# VC8Evrs4.net
KiCad netlist of a schematic drawn in EAGLE
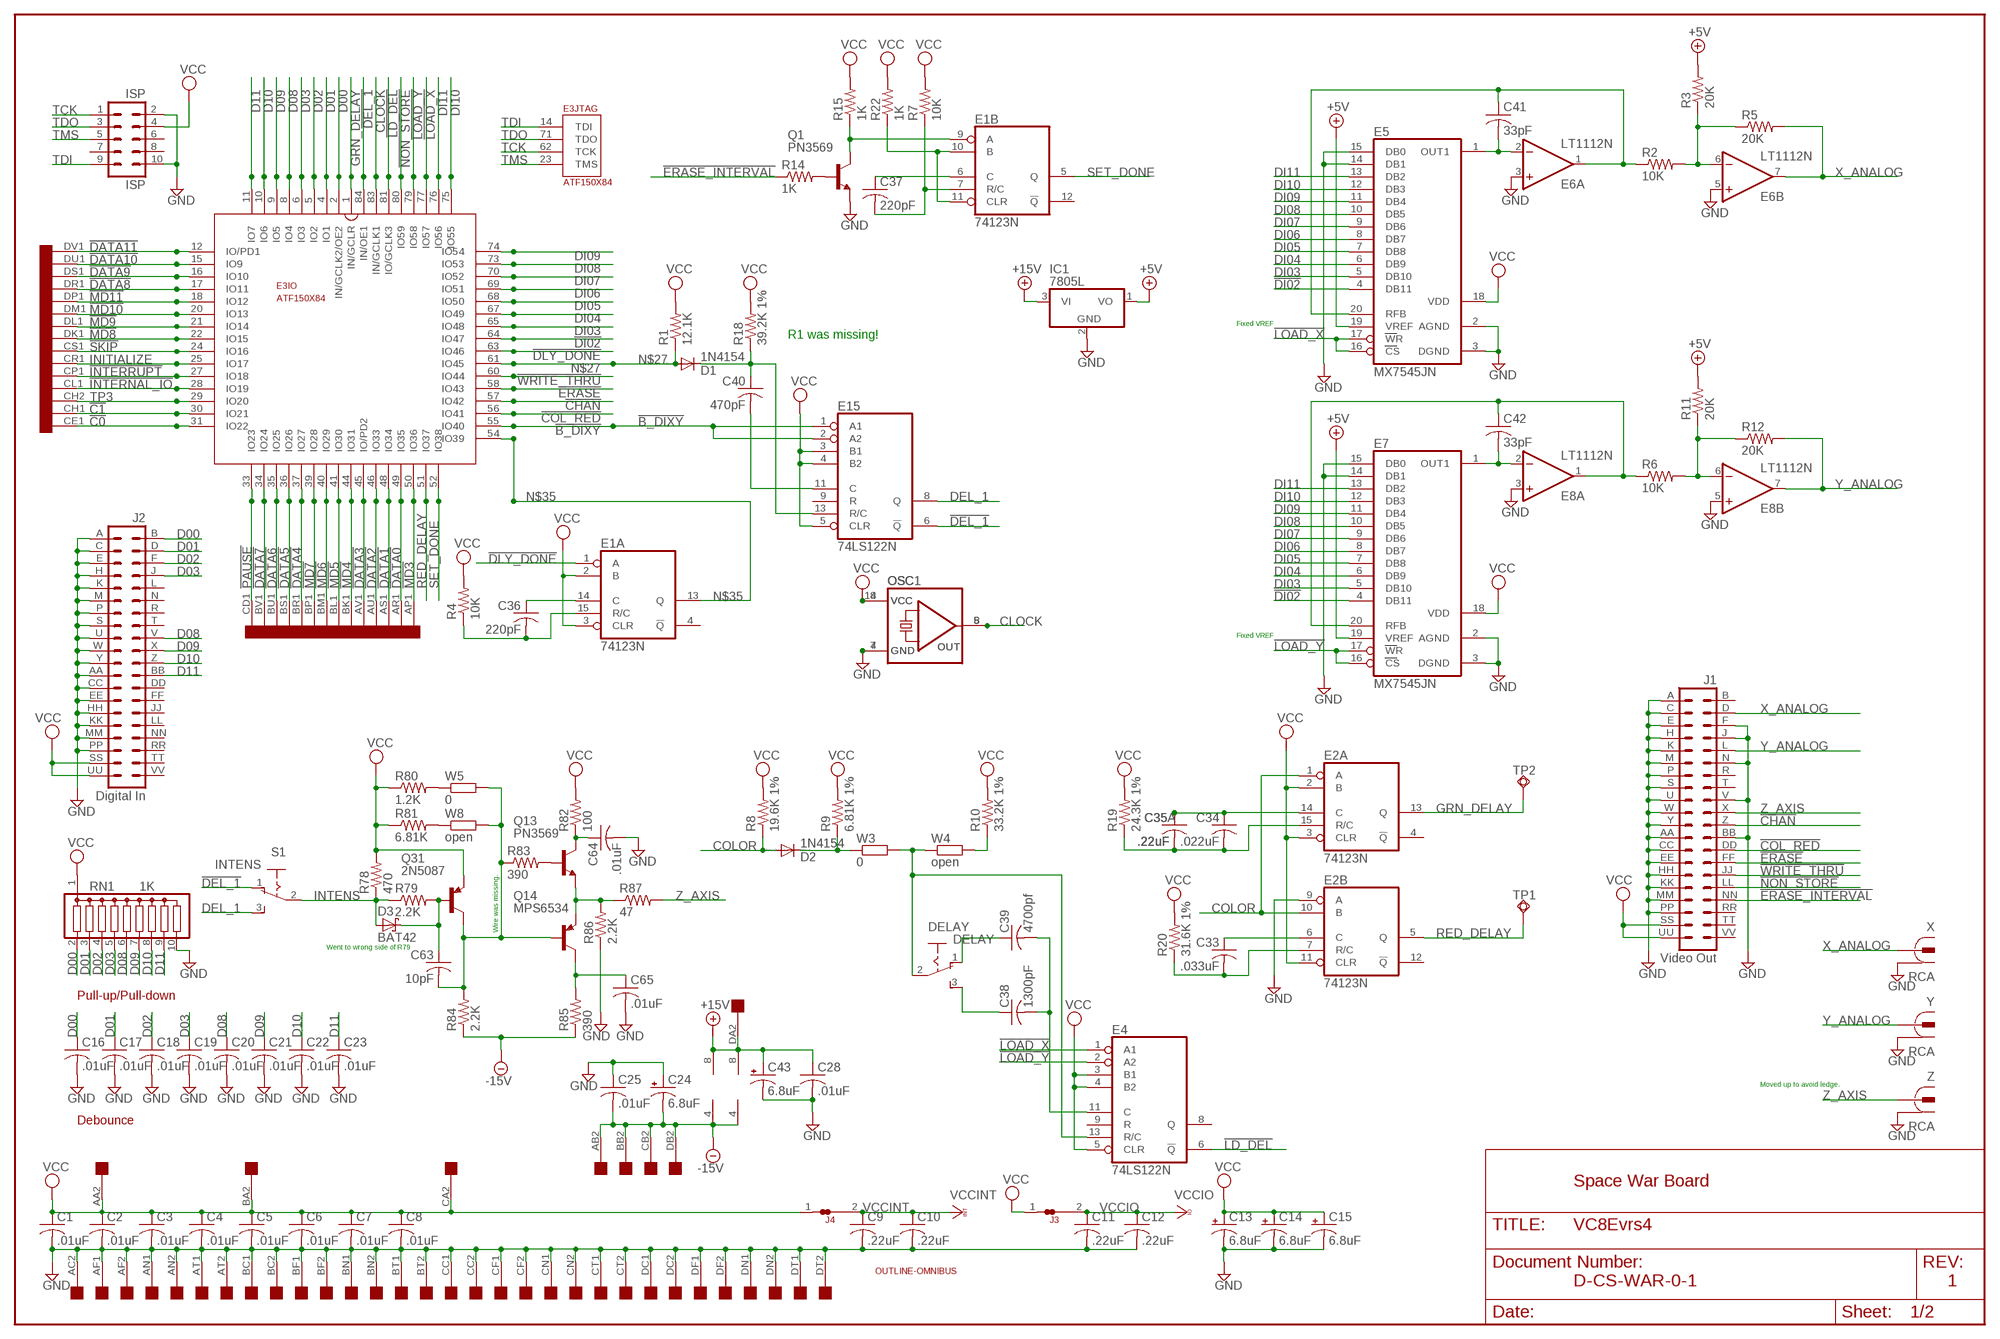
[diagram p0: schematic, sheet 1]

(export (version "E")
  (design (tool "Eeschema 10.0.6"))
  (components
    (comp (ref "C1")
      (value ".01uF")
      (footprint "eagle-import:C063-025X075")
      (libsource (lib "eagle-import") (part "C-US"))
    )
    (comp (ref "C2")
      (value ".01uF")
      (footprint "eagle-import:C063-025X075")
      (libsource (lib "eagle-import") (part "C-US"))
    )
    (comp (ref "C3")
      (value ".01uF")
      (footprint "eagle-import:C063-025X075")
      (libsource (lib "eagle-import") (part "C-US"))
    )
    (comp (ref "C4")
      (value ".01uF")
      (footprint "eagle-import:C063-025X075")
      (libsource (lib "eagle-import") (part "C-US"))
    )
    (comp (ref "C5")
      (value ".01uF")
      (footprint "eagle-import:C063-025X075")
      (libsource (lib "eagle-import") (part "C-US"))
    )
    (comp (ref "C6")
      (value ".01uF")
      (footprint "eagle-import:C063-025X075")
      (libsource (lib "eagle-import") (part "C-US"))
    )
    (comp (ref "C7")
      (value ".01uF")
      (footprint "eagle-import:C063-025X075")
      (libsource (lib "eagle-import") (part "C-US"))
    )
    (comp (ref "C8")
      (value ".01uF")
      (footprint "eagle-import:C063-025X075")
      (libsource (lib "eagle-import") (part "C-US"))
    )
    (comp (ref "C9")
      (value ".22uF")
      (footprint "eagle-import:C063-025X075")
      (libsource (lib "eagle-import") (part "C-US"))
    )
    (comp (ref "C10")
      (value ".22uF")
      (footprint "eagle-import:C063-025X075")
      (libsource (lib "eagle-import") (part "C-US"))
    )
    (comp (ref "C11")
      (value ".22uF")
      (footprint "eagle-import:C063-025X075")
      (libsource (lib "eagle-import") (part "C-US"))
    )
    (comp (ref "C12")
      (value ".22uF")
      (footprint "eagle-import:C063-025X075")
      (libsource (lib "eagle-import") (part "C-US"))
    )
    (comp (ref "C13")
      (value "6.8uF")
      (footprint "eagle-import:E12-8")
      (libsource (lib "eagle-import") (part "CPOL-USE20-8AXIAL"))
    )
    (comp (ref "C14")
      (value "6.8uF")
      (footprint "eagle-import:E12-8")
      (libsource (lib "eagle-import") (part "CPOL-USE20-8AXIAL"))
    )
    (comp (ref "C15")
      (value "6.8uF")
      (footprint "eagle-import:E12-8")
      (libsource (lib "eagle-import") (part "CPOL-USE20-8AXIAL"))
    )
    (comp (ref "C16")
      (value ".01uF")
      (footprint "eagle-import:C063-025X075")
      (libsource (lib "eagle-import") (part "C-US"))
    )
    (comp (ref "C17")
      (value ".01uF")
      (footprint "eagle-import:C063-025X075")
      (libsource (lib "eagle-import") (part "C-US"))
    )
    (comp (ref "C18")
      (value ".01uF")
      (footprint "eagle-import:C063-025X075")
      (libsource (lib "eagle-import") (part "C-US"))
    )
    (comp (ref "C19")
      (value ".01uF")
      (footprint "eagle-import:C063-025X075")
      (libsource (lib "eagle-import") (part "C-US"))
    )
    (comp (ref "C20")
      (value ".01uF")
      (footprint "eagle-import:C063-025X075")
      (libsource (lib "eagle-import") (part "C-US"))
    )
    (comp (ref "C21")
      (value ".01uF")
      (footprint "eagle-import:C063-025X075")
      (libsource (lib "eagle-import") (part "C-US"))
    )
    (comp (ref "C22")
      (value ".01uF")
      (footprint "eagle-import:C063-025X075")
      (libsource (lib "eagle-import") (part "C-US"))
    )
    (comp (ref "C23")
      (value ".01uF")
      (footprint "eagle-import:C063-025X075")
      (libsource (lib "eagle-import") (part "C-US"))
    )
    (comp (ref "C24")
      (value "6.8uF")
      (footprint "eagle-import:E12-8")
      (libsource (lib "eagle-import") (part "CPOL-USE20-8AXIAL"))
    )
    (comp (ref "C25")
      (value ".01uF")
      (footprint "eagle-import:C063-025X075")
      (libsource (lib "eagle-import") (part "C-US"))
    )
    (comp (ref "C28")
      (value ".01uF")
      (footprint "eagle-import:C063-025X075")
      (libsource (lib "eagle-import") (part "C-US"))
    )
    (comp (ref "C33")
      (value ".033uF")
      (footprint "eagle-import:C102-043X133")
      (libsource (lib "eagle-import") (part "C-US102-043X133"))
    )
    (comp (ref "C34")
      (value ".022uF")
      (footprint "eagle-import:C102-043X133")
      (libsource (lib "eagle-import") (part "C-US102-043X133"))
    )
    (comp (ref "C35")
      (value ".22uF")
      (footprint "eagle-import:C050-025X075")
      (libsource (lib "eagle-import") (part "C-US050-025X075"))
    )
    (comp (ref "C35A")
      (value ".22uF")
      (footprint "eagle-import:C102-043X133")
      (libsource (lib "eagle-import") (part "C-US102-043X133"))
    )
    (comp (ref "C36")
      (value "220pF")
      (footprint "eagle-import:C063-025X075")
      (libsource (lib "eagle-import") (part "C-US"))
    )
    (comp (ref "C37")
      (value "220pF")
      (footprint "eagle-import:C063-025X075")
      (libsource (lib "eagle-import") (part "C-US"))
    )
    (comp (ref "C38")
      (value "1300pF")
      (footprint "eagle-import:C150-054X183")
      (libsource (lib "eagle-import") (part "C-US150-054X183"))
    )
    (comp (ref "C39")
      (value "4700pf")
      (footprint "eagle-import:C102-043X133")
      (libsource (lib "eagle-import") (part "C-US102-043X133"))
    )
    (comp (ref "C40")
      (value "470pF")
      (footprint "eagle-import:C063-025X075")
      (libsource (lib "eagle-import") (part "C-US"))
    )
    (comp (ref "C41")
      (value "33pF")
      (footprint "eagle-import:C063-025X075")
      (libsource (lib "eagle-import") (part "C-US"))
    )
    (comp (ref "C42")
      (value "33pF")
      (footprint "eagle-import:C063-025X075")
      (libsource (lib "eagle-import") (part "C-US"))
    )
    (comp (ref "C43")
      (value "6.8uF")
      (footprint "eagle-import:E12-8")
      (libsource (lib "eagle-import") (part "CPOL-USE20-8AXIAL"))
    )
    (comp (ref "C63")
      (value "10pF")
      (footprint "eagle-import:C063-025X075")
      (libsource (lib "eagle-import") (part "C-US"))
    )
    (comp (ref "C64")
      (value ".01uF")
      (footprint "eagle-import:C063-025X075")
      (libsource (lib "eagle-import") (part "C-US"))
    )
    (comp (ref "C65")
      (value ".01uF")
      (footprint "eagle-import:C063-025X075")
      (libsource (lib "eagle-import") (part "C-US"))
    )
    (comp (ref "D1")
      (value "1N4154")
      (footprint "eagle-import:DO35-10")
      (libsource (lib "eagle-import") (part "DIODE-DO35-10"))
    )
    (comp (ref "D2")
      (value "1N4154")
      (footprint "eagle-import:DO35-10")
      (libsource (lib "eagle-import") (part "DIODE-DO35-10"))
    )
    (comp (ref "D3")
      (value "BAT42")
      (footprint "eagle-import:DO35-10")
      (libsource (lib "eagle-import") (part "BAT42"))
    )
    (comp (ref "DELAY")
      (value "DELAY")
      (footprint "eagle-import:M251")
      (libsource (lib "eagle-import") (part "M251"))
    )
    (comp (ref "E1")
      (value "74123N")
      (footprint "eagle-import:DIL16")
      (libsource (lib "eagle-import") (part "74123N"))
    )
    (comp (ref "E2")
      (value "74123N")
      (footprint "eagle-import:DIL16")
      (libsource (lib "eagle-import") (part "74123N"))
    )
    (comp (ref "E3")
      (value "ATF150X84")
      (footprint "eagle-import:S84")
      (libsource (lib "eagle-import") (part "ATF150X84"))
    )
    (comp (ref "E4")
      (value "74LS122N")
      (footprint "eagle-import:DIL14")
      (libsource (lib "eagle-import") (part "74122NLS"))
    )
    (comp (ref "E5")
      (value "MX7545JN")
      (footprint "eagle-import:DIL20")
      (fields (field (name "MPN") "MX7545JN+"))
      (libsource (lib "eagle-import") (part "MX7545JN"))
    )
    (comp (ref "E6")
      (value "LT1112N")
      (footprint "eagle-import:DIL08")
      (libsource (lib "eagle-import") (part "1458NLM"))
    )
    (comp (ref "E7")
      (value "MX7545JN")
      (footprint "eagle-import:DIL20")
      (fields (field (name "MPN") "MX7545JN+"))
      (libsource (lib "eagle-import") (part "MX7545JN"))
    )
    (comp (ref "E8")
      (value "LT1112N")
      (footprint "eagle-import:DIL08")
      (libsource (lib "eagle-import") (part "1458NLM"))
    )
    (comp (ref "E15")
      (value "74LS122N")
      (footprint "eagle-import:DIL14")
      (libsource (lib "eagle-import") (part "74122NLS"))
    )
    (comp (ref "IC1")
      (value "7805L")
      (footprint "eagle-import:TO92")
      (libsource (lib "eagle-import") (part "78L05"))
    )
    (comp (ref "ISP")
      (value "ISP")
      (footprint "eagle-import:ML10")
      (libsource (lib "eagle-import") (part "ML10"))
    )
    (comp (ref "J1")
      (value "Video Out")
      (footprint "eagle-import:DEC40PINH")
      (libsource (lib "eagle-import") (part "DEC40PINH"))
    )
    (comp (ref "J2")
      (value "Digital In")
      (footprint "eagle-import:DEC40PINH")
      (libsource (lib "eagle-import") (part "DEC40PINH"))
    )
    (comp (ref "J3")
      (value "JUMPER-NC1")
      (footprint "eagle-import:NC1")
      (libsource (lib "eagle-import") (part "JUMPER-NC1"))
    )
    (comp (ref "J4")
      (value "JUMPER-NC1")
      (footprint "eagle-import:NC1")
      (libsource (lib "eagle-import") (part "JUMPER-NC1"))
    )
    (comp (ref "OMNIBUS")
      (value "QUAD")
      (footprint "eagle-import:EDGE-CON8")
      (libsource (lib "eagle-import") (part "QUAD"))
    )
    (comp (ref "OSC")
      (value "QG5460")
      (footprint "eagle-import:DIL08S")
      (libsource (lib "eagle-import") (part "QG5460"))
    )
    (comp (ref "OSC1")
      (value "QG5860")
      (footprint "eagle-import:DIL14S")
      (libsource (lib "eagle-import") (part "QG5860"))
    )
    (comp (ref "Q1")
      (value "PN3569")
      (footprint "eagle-import:TO5")
      (libsource (lib "eagle-import") (part "-NPN-TO5"))
    )
    (comp (ref "Q13")
      (value "PN3569")
      (footprint "eagle-import:TO5")
      (libsource (lib "eagle-import") (part "-NPN-TO5"))
    )
    (comp (ref "Q14")
      (value "MPS6534")
      (footprint "eagle-import:TO5")
      (libsource (lib "eagle-import") (part "-PNP-TO5"))
    )
    (comp (ref "Q31")
      (value "2N5087")
      (footprint "eagle-import:TO5")
      (libsource (lib "eagle-import") (part "-PNP-TO5"))
    )
    (comp (ref "R1")
      (value "12.1K")
      (footprint "eagle-import:0207_15")
      (libsource (lib "eagle-import") (part "R-US_0207/15"))
    )
    (comp (ref "R2")
      (value "10K")
      (footprint "eagle-import:0207_10")
      (libsource (lib "eagle-import") (part "R-US_0207/10"))
    )
    (comp (ref "R3")
      (value "20K")
      (footprint "eagle-import:0207_10")
      (libsource (lib "eagle-import") (part "R-US_0207/10"))
    )
    (comp (ref "R4")
      (value "10K")
      (footprint "eagle-import:0207_10")
      (libsource (lib "eagle-import") (part "R-US_0207/10"))
    )
    (comp (ref "R5")
      (value "20K")
      (footprint "eagle-import:0207_10")
      (libsource (lib "eagle-import") (part "R-US_0207/10"))
    )
    (comp (ref "R6")
      (value "10K")
      (footprint "eagle-import:0207_10")
      (libsource (lib "eagle-import") (part "R-US_0207/10"))
    )
    (comp (ref "R7")
      (value "10K")
      (footprint "eagle-import:0207_10")
      (libsource (lib "eagle-import") (part "R-US_0207/10"))
    )
    (comp (ref "R8")
      (value "19.6K 1%")
      (footprint "eagle-import:0207_15")
      (libsource (lib "eagle-import") (part "R-US_0207/15"))
    )
    (comp (ref "R9")
      (value "6.81K 1%")
      (footprint "eagle-import:0207_15")
      (libsource (lib "eagle-import") (part "R-US_0207/15"))
    )
    (comp (ref "R10")
      (value "33.2K 1%")
      (footprint "eagle-import:0207_15")
      (libsource (lib "eagle-import") (part "R-US_0207/15"))
    )
    (comp (ref "R11")
      (value "20K")
      (footprint "eagle-import:0207_10")
      (libsource (lib "eagle-import") (part "R-US_0207/10"))
    )
    (comp (ref "R12")
      (value "20K")
      (footprint "eagle-import:0207_10")
      (libsource (lib "eagle-import") (part "R-US_0207/10"))
    )
    (comp (ref "R14")
      (value "1K")
      (footprint "eagle-import:0207_10")
      (libsource (lib "eagle-import") (part "R-US_0207/10"))
    )
    (comp (ref "R15")
      (value "1K")
      (footprint "eagle-import:0207_10")
      (libsource (lib "eagle-import") (part "R-US_0207/10"))
    )
    (comp (ref "R18")
      (value "39.2K 1%")
      (footprint "eagle-import:0207_15")
      (libsource (lib "eagle-import") (part "R-US_0207/15"))
    )
    (comp (ref "R19")
      (value "24.3K 1%")
      (footprint "eagle-import:0207_15")
      (libsource (lib "eagle-import") (part "R-US_0207/15"))
    )
    (comp (ref "R20")
      (value "31.6K 1%")
      (footprint "eagle-import:0207_15")
      (libsource (lib "eagle-import") (part "R-US_0207/15"))
    )
    (comp (ref "R22")
      (value "1K")
      (footprint "eagle-import:0207_10")
      (libsource (lib "eagle-import") (part "R-US_0207/10"))
    )
    (comp (ref "R78")
      (value "470")
      (footprint "eagle-import:0207_10")
      (libsource (lib "eagle-import") (part "R-US_0207/10"))
    )
    (comp (ref "R79")
      (value "2.2K")
      (footprint "eagle-import:0207_10")
      (libsource (lib "eagle-import") (part "R-US_0207/10"))
    )
    (comp (ref "R80")
      (value "1.2K")
      (footprint "eagle-import:0207_10")
      (libsource (lib "eagle-import") (part "R-US_0207/10"))
    )
    (comp (ref "R81")
      (value "6.81K")
      (footprint "eagle-import:0207_10")
      (libsource (lib "eagle-import") (part "R-US_0207/10"))
    )
    (comp (ref "R82")
      (value "100")
      (footprint "eagle-import:0207_10")
      (libsource (lib "eagle-import") (part "R-US_0207/10"))
    )
    (comp (ref "R83")
      (value "390")
      (footprint "eagle-import:0207_10")
      (libsource (lib "eagle-import") (part "R-US_0207/10"))
    )
    (comp (ref "R84")
      (value "2.2K")
      (footprint "eagle-import:0207_10")
      (libsource (lib "eagle-import") (part "R-US_0207/10"))
    )
    (comp (ref "R85")
      (value "390")
      (footprint "eagle-import:0207_10")
      (libsource (lib "eagle-import") (part "R-US_0207/10"))
    )
    (comp (ref "R86")
      (value "2.2K")
      (footprint "eagle-import:0207_10")
      (libsource (lib "eagle-import") (part "R-US_0207/10"))
    )
    (comp (ref "R87")
      (value "47")
      (footprint "eagle-import:0207_10")
      (libsource (lib "eagle-import") (part "R-US_0207/10"))
    )
    (comp (ref "RN1")
      (value "1K")
      (footprint "eagle-import:SIL10")
      (libsource (lib "eagle-import") (part "G09R"))
    )
    (comp (ref "S1")
      (value "INTENS")
      (footprint "eagle-import:M251")
      (libsource (lib "eagle-import") (part "M251"))
    )
    (comp (ref "TP1")
      (value "TPSQPAD1-17")
      (footprint "eagle-import:P1-17")
      (libsource (lib "eagle-import") (part "TPSQPAD1-17"))
    )
    (comp (ref "TP2")
      (value "TPSQPAD1-17")
      (footprint "eagle-import:P1-17")
      (libsource (lib "eagle-import") (part "TPSQPAD1-17"))
    )
    (comp (ref "U$1")
      (value "OUTLINE-OMNIBUS")
      (footprint "eagle-import:OMNIBUS")
      (libsource (lib "eagle-import") (part "OUTLINE-OMNIBUS"))
    )
    (comp (ref "W3")
      (value "0")
      (footprint "eagle-import:0207_10")
      (libsource (lib "eagle-import") (part "R-EU_0207/10"))
    )
    (comp (ref "W4")
      (value "open")
      (footprint "eagle-import:0207_10")
      (libsource (lib "eagle-import") (part "R-EU_0207/10"))
    )
    (comp (ref "W5")
      (value "0")
      (footprint "eagle-import:0207_10")
      (libsource (lib "eagle-import") (part "R-EU_0207/10"))
    )
    (comp (ref "W8")
      (value "open")
      (footprint "eagle-import:0207_10")
      (libsource (lib "eagle-import") (part "R-EU_0207/10"))
    )
    (comp (ref "X")
      (value "RCA")
      (footprint "eagle-import:RCA")
      (libsource (lib "eagle-import") (part "RCA"))
    )
    (comp (ref "Y")
      (value "RCA")
      (footprint "eagle-import:RCA")
      (libsource (lib "eagle-import") (part "RCA"))
    )
    (comp (ref "Z")
      (value "RCA")
      (footprint "eagle-import:RCA")
      (libsource (lib "eagle-import") (part "RCA"))
    )
  )
  (nets
    (net (code "1") (name "+5V") (class "Default")
      (node (ref "E5") (pin "19") (pinfunction "VREF_19") (pintype "input"))
      (node (ref "E7") (pin "19") (pinfunction "VREF_19") (pintype "input"))
      (node (ref "IC1") (pin "1") (pinfunction "VO_1") (pintype "passive"))
      (node (ref "R11") (pin "2") (pinfunction "2_2") (pintype "passive"))
      (node (ref "R3") (pin "2") (pinfunction "2_2") (pintype "passive"))
    )
    (net (code "2") (name "+15V") (class "Default")
      (node (ref "C28") (pin "1") (pinfunction "1_1") (pintype "passive"))
      (node (ref "C43") (pin "+") (pinfunction "+_+") (pintype "passive"))
      (node (ref "E6") (pin "8") (pinfunction "V+_8") (pintype "power_in"))
      (node (ref "E8") (pin "8") (pinfunction "V+_8") (pintype "power_in"))
      (node (ref "IC1") (pin "3") (pinfunction "VI_3") (pintype "input"))
      (node (ref "OMNIBUS") (pin "DA2") (pinfunction "1_DA2") (pintype "bidirectional"))
    )
    (net (code "3") (name "-15V") (class "Default")
      (node (ref "C24") (pin "-") (pinfunction "-_-") (pintype "passive"))
      (node (ref "C25") (pin "2") (pinfunction "2_2") (pintype "passive"))
      (node (ref "E6") (pin "4") (pinfunction "V-_4") (pintype "power_in"))
      (node (ref "E8") (pin "4") (pinfunction "V-_4") (pintype "power_in"))
      (node (ref "OMNIBUS") (pin "AB2") (pinfunction "1_AB2") (pintype "bidirectional"))
      (node (ref "OMNIBUS") (pin "BB2") (pinfunction "1_BB2") (pintype "bidirectional"))
      (node (ref "OMNIBUS") (pin "CB2") (pinfunction "1_CB2") (pintype "bidirectional"))
      (node (ref "OMNIBUS") (pin "DB2") (pinfunction "1_DB2") (pintype "bidirectional"))
      (node (ref "R84") (pin "1") (pinfunction "1_1") (pintype "passive"))
      (node (ref "R85") (pin "1") (pinfunction "1_1") (pintype "passive"))
    )
    (net (code "4") (name "CLOCK") (class "Default")
      (node (ref "E3") (pin "83") (pinfunction "IN/GCLK1_83") (pintype "input"))
      (node (ref "OSC") (pin "5") (pinfunction "OUT_5") (pintype "output"))
      (node (ref "OSC1") (pin "8") (pinfunction "OUT_8") (pintype "output"))
    )
    (net (code "5") (name "COLOR") (class "Default")
      (node (ref "D2") (pin "A") (pinfunction "A_A") (pintype "passive"))
      (node (ref "E2") (pin "1") (pinfunction "A_1") (pintype "input"))
      (node (ref "E2") (pin "10") (pinfunction "B_10") (pintype "input"))
      (node (ref "R8") (pin "1") (pinfunction "1_1") (pintype "passive"))
    )
    (net (code "6") (name "D00") (class "Default")
      (node (ref "C16") (pin "1") (pinfunction "1_1") (pintype "passive"))
      (node (ref "E3") (pin "2") (pinfunction "IN/GCLK2/OE2_2") (pintype "input"))
      (node (ref "J2") (pin "B") (pinfunction "2_B") (pintype "bidirectional"))
      (node (ref "RN1") (pin "2") (pinfunction "2_2") (pintype "passive"))
    )
    (net (code "7") (name "D01") (class "Default")
      (node (ref "C17") (pin "1") (pinfunction "1_1") (pintype "passive"))
      (node (ref "E3") (pin "4") (pinfunction "IO1_4") (pintype "bidirectional"))
      (node (ref "J2") (pin "D") (pinfunction "4_D") (pintype "bidirectional"))
      (node (ref "RN1") (pin "3") (pinfunction "3_3") (pintype "passive"))
    )
    (net (code "8") (name "D02") (class "Default")
      (node (ref "C18") (pin "1") (pinfunction "1_1") (pintype "passive"))
      (node (ref "E3") (pin "5") (pinfunction "IO2_5") (pintype "bidirectional"))
      (node (ref "J2") (pin "F") (pinfunction "6_F") (pintype "bidirectional"))
      (node (ref "RN1") (pin "4") (pinfunction "4_4") (pintype "passive"))
    )
    (net (code "9") (name "D03") (class "Default")
      (node (ref "C19") (pin "1") (pinfunction "1_1") (pintype "passive"))
      (node (ref "E3") (pin "6") (pinfunction "IO3_6") (pintype "bidirectional"))
      (node (ref "J2") (pin "J") (pinfunction "8_J") (pintype "bidirectional"))
      (node (ref "RN1") (pin "5") (pinfunction "5_5") (pintype "passive"))
    )
    (net (code "10") (name "D08") (class "Default")
      (node (ref "C20") (pin "1") (pinfunction "1_1") (pintype "passive"))
      (node (ref "E3") (pin "8") (pinfunction "IO4_8") (pintype "bidirectional"))
      (node (ref "J2") (pin "V") (pinfunction "18_V") (pintype "bidirectional"))
      (node (ref "RN1") (pin "6") (pinfunction "6_6") (pintype "passive"))
    )
    (net (code "11") (name "D09") (class "Default")
      (node (ref "C21") (pin "1") (pinfunction "1_1") (pintype "passive"))
      (node (ref "E3") (pin "9") (pinfunction "IO5_9") (pintype "bidirectional"))
      (node (ref "J2") (pin "X") (pinfunction "20_X") (pintype "bidirectional"))
      (node (ref "RN1") (pin "7") (pinfunction "7_7") (pintype "passive"))
    )
    (net (code "12") (name "D10") (class "Default")
      (node (ref "C22") (pin "1") (pinfunction "1_1") (pintype "passive"))
      (node (ref "E3") (pin "10") (pinfunction "IO6_10") (pintype "bidirectional"))
      (node (ref "J2") (pin "Z") (pinfunction "22_Z") (pintype "bidirectional"))
      (node (ref "RN1") (pin "8") (pinfunction "8_8") (pintype "passive"))
    )
    (net (code "13") (name "D11") (class "Default")
      (node (ref "C23") (pin "1") (pinfunction "1_1") (pintype "passive"))
      (node (ref "E3") (pin "11") (pinfunction "IO7_11") (pintype "bidirectional"))
      (node (ref "J2") (pin "BB") (pinfunction "24_BB") (pintype "bidirectional"))
      (node (ref "RN1") (pin "9") (pinfunction "9_9") (pintype "passive"))
    )
    (net (code "14") (name "DEL_1") (class "Default")
      (node (ref "E15") (pin "8") (pinfunction "Q_8") (pintype "output"))
      (node (ref "S1") (pin "3") (pinfunction "S_3") (pintype "passive"))
    )
    (net (code "15") (name "DI03") (class "Default")
      (node (ref "E3") (pin "65") (pinfunction "IO48_65") (pintype "bidirectional"))
      (node (ref "E5") (pin "5") (pinfunction "DB10_5") (pintype "input"))
      (node (ref "E7") (pin "5") (pinfunction "DB10_5") (pintype "input"))
    )
    (net (code "16") (name "DI04") (class "Default")
      (node (ref "E3") (pin "67") (pinfunction "IO49_67") (pintype "bidirectional"))
      (node (ref "E5") (pin "6") (pinfunction "DB9_6") (pintype "input"))
      (node (ref "E7") (pin "6") (pinfunction "DB9_6") (pintype "input"))
    )
    (net (code "17") (name "DI05") (class "Default")
      (node (ref "E3") (pin "68") (pinfunction "IO50_68") (pintype "bidirectional"))
      (node (ref "E5") (pin "7") (pinfunction "DB8_7") (pintype "input"))
      (node (ref "E7") (pin "7") (pinfunction "DB8_7") (pintype "input"))
    )
    (net (code "18") (name "DI06") (class "Default")
      (node (ref "E3") (pin "69") (pinfunction "IO51_69") (pintype "bidirectional"))
      (node (ref "E5") (pin "8") (pinfunction "DB7_8") (pintype "input"))
      (node (ref "E7") (pin "8") (pinfunction "DB7_8") (pintype "input"))
    )
    (net (code "19") (name "DI07") (class "Default")
      (node (ref "E3") (pin "70") (pinfunction "IO52_70") (pintype "bidirectional"))
      (node (ref "E5") (pin "9") (pinfunction "DB6_9") (pintype "input"))
      (node (ref "E7") (pin "9") (pinfunction "DB6_9") (pintype "input"))
    )
    (net (code "20") (name "DI08") (class "Default")
      (node (ref "E3") (pin "73") (pinfunction "IO53_73") (pintype "bidirectional"))
      (node (ref "E5") (pin "10") (pinfunction "DB5_10") (pintype "input"))
      (node (ref "E7") (pin "10") (pinfunction "DB5_10") (pintype "input"))
    )
    (net (code "21") (name "DI09") (class "Default")
      (node (ref "E3") (pin "74") (pinfunction "IO54_74") (pintype "bidirectional"))
      (node (ref "E5") (pin "11") (pinfunction "DB4_11") (pintype "input"))
      (node (ref "E7") (pin "11") (pinfunction "DB4_11") (pintype "input"))
    )
    (net (code "22") (name "DI10") (class "Default")
      (node (ref "E3") (pin "75") (pinfunction "IO55_75") (pintype "bidirectional"))
      (node (ref "E5") (pin "12") (pinfunction "DB3_12") (pintype "input"))
      (node (ref "E7") (pin "12") (pinfunction "DB3_12") (pintype "input"))
    )
    (net (code "23") (name "DI11") (class "Default")
      (node (ref "E3") (pin "76") (pinfunction "IO56_76") (pintype "bidirectional"))
      (node (ref "E5") (pin "13") (pinfunction "DB2_13") (pintype "input"))
      (node (ref "E7") (pin "13") (pinfunction "DB2_13") (pintype "input"))
    )
    (net (code "24") (name "GND") (class "Default")
      (node (ref "C1") (pin "2") (pinfunction "2_2") (pintype "passive"))
      (node (ref "C10") (pin "2") (pinfunction "2_2") (pintype "passive"))
      (node (ref "C11") (pin "2") (pinfunction "2_2") (pintype "passive"))
      (node (ref "C12") (pin "2") (pinfunction "2_2") (pintype "passive"))
      (node (ref "C13") (pin "-") (pinfunction "-_-") (pintype "passive"))
      (node (ref "C14") (pin "-") (pinfunction "-_-") (pintype "passive"))
      (node (ref "C15") (pin "-") (pinfunction "-_-") (pintype "passive"))
      (node (ref "C16") (pin "2") (pinfunction "2_2") (pintype "passive"))
      (node (ref "C17") (pin "2") (pinfunction "2_2") (pintype "passive"))
      (node (ref "C18") (pin "2") (pinfunction "2_2") (pintype "passive"))
      (node (ref "C19") (pin "2") (pinfunction "2_2") (pintype "passive"))
      (node (ref "C2") (pin "2") (pinfunction "2_2") (pintype "passive"))
      (node (ref "C20") (pin "2") (pinfunction "2_2") (pintype "passive"))
      (node (ref "C21") (pin "2") (pinfunction "2_2") (pintype "passive"))
      (node (ref "C22") (pin "2") (pinfunction "2_2") (pintype "passive"))
      (node (ref "C23") (pin "2") (pinfunction "2_2") (pintype "passive"))
      (node (ref "C24") (pin "+") (pinfunction "+_+") (pintype "passive"))
      (node (ref "C25") (pin "1") (pinfunction "1_1") (pintype "passive"))
      (node (ref "C28") (pin "2") (pinfunction "2_2") (pintype "passive"))
      (node (ref "C3") (pin "2") (pinfunction "2_2") (pintype "passive"))
      (node (ref "C4") (pin "2") (pinfunction "2_2") (pintype "passive"))
      (node (ref "C43") (pin "-") (pinfunction "-_-") (pintype "passive"))
      (node (ref "C5") (pin "2") (pinfunction "2_2") (pintype "passive"))
      (node (ref "C6") (pin "2") (pinfunction "2_2") (pintype "passive"))
      (node (ref "C64") (pin "2") (pinfunction "2_2") (pintype "passive"))
      (node (ref "C65") (pin "2") (pinfunction "2_2") (pintype "passive"))
      (node (ref "C7") (pin "2") (pinfunction "2_2") (pintype "passive"))
      (node (ref "C8") (pin "2") (pinfunction "2_2") (pintype "passive"))
      (node (ref "C9") (pin "2") (pinfunction "2_2") (pintype "passive"))
      (node (ref "E2") (pin "9") (pinfunction "A_9") (pintype "input"))
      (node (ref "E5") (pin "14") (pinfunction "DB1_14") (pintype "input"))
      (node (ref "E5") (pin "15") (pinfunction "DB0_15") (pintype "input"))
      (node (ref "E5") (pin "2") (pinfunction "AGND_2") (pintype "power_in"))
      (node (ref "E5") (pin "3") (pinfunction "DGND_3") (pintype "power_in"))
      (node (ref "E6") (pin "3") (pinfunction "+IN_3") (pintype "input"))
      (node (ref "E6") (pin "5") (pinfunction "+IN_5") (pintype "input"))
      (node (ref "E7") (pin "14") (pinfunction "DB1_14") (pintype "input"))
      (node (ref "E7") (pin "15") (pinfunction "DB0_15") (pintype "input"))
      (node (ref "E7") (pin "2") (pinfunction "AGND_2") (pintype "power_in"))
      (node (ref "E7") (pin "3") (pinfunction "DGND_3") (pintype "power_in"))
      (node (ref "E8") (pin "3") (pinfunction "+IN_3") (pintype "input"))
      (node (ref "E8") (pin "5") (pinfunction "+IN_5") (pintype "input"))
      (node (ref "IC1") (pin "2") (pinfunction "GND_2") (pintype "passive"))
      (node (ref "ISP") (pin "10") (pinfunction "10_10") (pintype "passive"))
      (node (ref "ISP") (pin "2") (pinfunction "2_2") (pintype "passive"))
      (node (ref "J1") (pin "A") (pinfunction "1_A") (pintype "bidirectional"))
      (node (ref "J1") (pin "AA") (pinfunction "23_AA") (pintype "bidirectional"))
      (node (ref "J1") (pin "BB") (pinfunction "24_BB") (pintype "bidirectional"))
      (node (ref "J1") (pin "C") (pinfunction "3_C") (pintype "bidirectional"))
      (node (ref "J1") (pin "CC") (pinfunction "25_CC") (pintype "bidirectional"))
      (node (ref "J1") (pin "E") (pinfunction "5_E") (pintype "bidirectional"))
      (node (ref "J1") (pin "EE") (pinfunction "27_EE") (pintype "bidirectional"))
      (node (ref "J1") (pin "F") (pinfunction "6_F") (pintype "bidirectional"))
      (node (ref "J1") (pin "H") (pinfunction "7_H") (pintype "bidirectional"))
      (node (ref "J1") (pin "HH") (pinfunction "29_HH") (pintype "bidirectional"))
      (node (ref "J1") (pin "J") (pinfunction "8_J") (pintype "bidirectional"))
      (node (ref "J1") (pin "K") (pinfunction "9_K") (pintype "bidirectional"))
      (node (ref "J1") (pin "KK") (pinfunction "31_KK") (pintype "bidirectional"))
      (node (ref "J1") (pin "M") (pinfunction "11_M") (pintype "bidirectional"))
      (node (ref "J1") (pin "MM") (pinfunction "33_MM") (pintype "bidirectional"))
      (node (ref "J1") (pin "N") (pinfunction "12_N") (pintype "bidirectional"))
      (node (ref "J1") (pin "P") (pinfunction "13_P") (pintype "bidirectional"))
      (node (ref "J1") (pin "PP") (pinfunction "35_PP") (pintype "bidirectional"))
      (node (ref "J1") (pin "S") (pinfunction "15_S") (pintype "bidirectional"))
      (node (ref "J1") (pin "U") (pinfunction "17_U") (pintype "bidirectional"))
      (node (ref "J1") (pin "V") (pinfunction "18_V") (pintype "bidirectional"))
      (node (ref "J1") (pin "W") (pinfunction "19_W") (pintype "bidirectional"))
      (node (ref "J1") (pin "Y") (pinfunction "21_Y") (pintype "bidirectional"))
      (node (ref "J2") (pin "A") (pinfunction "1_A") (pintype "bidirectional"))
      (node (ref "J2") (pin "AA") (pinfunction "23_AA") (pintype "bidirectional"))
      (node (ref "J2") (pin "C") (pinfunction "3_C") (pintype "bidirectional"))
      (node (ref "J2") (pin "CC") (pinfunction "25_CC") (pintype "bidirectional"))
      (node (ref "J2") (pin "E") (pinfunction "5_E") (pintype "bidirectional"))
      (node (ref "J2") (pin "EE") (pinfunction "27_EE") (pintype "bidirectional"))
      (node (ref "J2") (pin "H") (pinfunction "7_H") (pintype "bidirectional"))
      (node (ref "J2") (pin "HH") (pinfunction "29_HH") (pintype "bidirectional"))
      (node (ref "J2") (pin "K") (pinfunction "9_K") (pintype "bidirectional"))
      (node (ref "J2") (pin "KK") (pinfunction "31_KK") (pintype "bidirectional"))
      (node (ref "J2") (pin "M") (pinfunction "11_M") (pintype "bidirectional"))
      (node (ref "J2") (pin "MM") (pinfunction "33_MM") (pintype "bidirectional"))
      (node (ref "J2") (pin "P") (pinfunction "13_P") (pintype "bidirectional"))
      (node (ref "J2") (pin "PP") (pinfunction "35_PP") (pintype "bidirectional"))
      (node (ref "J2") (pin "S") (pinfunction "15_S") (pintype "bidirectional"))
      (node (ref "J2") (pin "U") (pinfunction "17_U") (pintype "bidirectional"))
      (node (ref "J2") (pin "W") (pinfunction "19_W") (pintype "bidirectional"))
      (node (ref "J2") (pin "Y") (pinfunction "21_Y") (pintype "bidirectional"))
      (node (ref "OMNIBUS") (pin "AC2") (pinfunction "1_AC2") (pintype "bidirectional"))
      (node (ref "OMNIBUS") (pin "AF1") (pinfunction "1_AF1") (pintype "bidirectional"))
      (node (ref "OMNIBUS") (pin "AF2") (pinfunction "1_AF2") (pintype "bidirectional"))
      (node (ref "OMNIBUS") (pin "AN1") (pinfunction "1_AN1") (pintype "bidirectional"))
      (node (ref "OMNIBUS") (pin "AN2") (pinfunction "1_AN2") (pintype "bidirectional"))
      (node (ref "OMNIBUS") (pin "AT1") (pinfunction "1_AT1") (pintype "bidirectional"))
      (node (ref "OMNIBUS") (pin "AT2") (pinfunction "1_AT2") (pintype "bidirectional"))
      (node (ref "OMNIBUS") (pin "BC1") (pinfunction "1_BC1") (pintype "bidirectional"))
      (node (ref "OMNIBUS") (pin "BC2") (pinfunction "1_BC2") (pintype "bidirectional"))
      (node (ref "OMNIBUS") (pin "BF1") (pinfunction "1_BF1") (pintype "bidirectional"))
      (node (ref "OMNIBUS") (pin "BF2") (pinfunction "1_BF2") (pintype "bidirectional"))
      (node (ref "OMNIBUS") (pin "BN1") (pinfunction "1_BN1") (pintype "bidirectional"))
      (node (ref "OMNIBUS") (pin "BN2") (pinfunction "1_BN2") (pintype "bidirectional"))
      (node (ref "OMNIBUS") (pin "BT1") (pinfunction "1_BT1") (pintype "bidirectional"))
      (node (ref "OMNIBUS") (pin "BT2") (pinfunction "1_BT2") (pintype "bidirectional"))
      (node (ref "OMNIBUS") (pin "CC1") (pinfunction "1_CC1") (pintype "bidirectional"))
      (node (ref "OMNIBUS") (pin "CC2") (pinfunction "1_CC2") (pintype "bidirectional"))
      (node (ref "OMNIBUS") (pin "CF1") (pinfunction "1_CF1") (pintype "bidirectional"))
      (node (ref "OMNIBUS") (pin "CF2") (pinfunction "1_CF2") (pintype "bidirectional"))
      (node (ref "OMNIBUS") (pin "CN1") (pinfunction "1_CN1") (pintype "bidirectional"))
      (node (ref "OMNIBUS") (pin "CN2") (pinfunction "1_CN2") (pintype "bidirectional"))
      (node (ref "OMNIBUS") (pin "CT1") (pinfunction "1_CT1") (pintype "bidirectional"))
      (node (ref "OMNIBUS") (pin "CT2") (pinfunction "1_CT2") (pintype "bidirectional"))
      (node (ref "OMNIBUS") (pin "DC1") (pinfunction "1_DC1") (pintype "bidirectional"))
      (node (ref "OMNIBUS") (pin "DC2") (pinfunction "1_DC2") (pintype "bidirectional"))
      (node (ref "OMNIBUS") (pin "DF1") (pinfunction "1_DF1") (pintype "bidirectional"))
      (node (ref "OMNIBUS") (pin "DF2") (pinfunction "1_DF2") (pintype "bidirectional"))
      (node (ref "OMNIBUS") (pin "DN1") (pinfunction "1_DN1") (pintype "bidirectional"))
      (node (ref "OMNIBUS") (pin "DN2") (pinfunction "1_DN2") (pintype "bidirectional"))
      (node (ref "OMNIBUS") (pin "DT1") (pinfunction "1_DT1") (pintype "bidirectional"))
      (node (ref "OMNIBUS") (pin "DT2") (pinfunction "1_DT2") (pintype "bidirectional"))
      (node (ref "OSC") (pin "4") (pinfunction "GND_4") (pintype "power_in"))
      (node (ref "OSC1") (pin "7") (pinfunction "GND_7") (pintype "power_in"))
      (node (ref "Q1") (pin "1") (pinfunction "E_1") (pintype "passive"))
      (node (ref "R86") (pin "1") (pinfunction "1_1") (pintype "passive"))
      (node (ref "RN1") (pin "10") (pinfunction "10_10") (pintype "passive"))
      (node (ref "X") (pin "1") (pinfunction "1_1") (pintype "passive"))
      (node (ref "X") (pin "1@1") (pinfunction "1_1@1") (pintype "passive"))
      (node (ref "X") (pin "1@2") (pinfunction "1_1@2") (pintype "passive"))
      (node (ref "Y") (pin "1") (pinfunction "1_1") (pintype "passive"))
      (node (ref "Y") (pin "1@1") (pinfunction "1_1@1") (pintype "passive"))
      (node (ref "Y") (pin "1@2") (pinfunction "1_1@2") (pintype "passive"))
      (node (ref "Z") (pin "1") (pinfunction "1_1") (pintype "passive"))
      (node (ref "Z") (pin "1@1") (pinfunction "1_1@1") (pintype "passive"))
      (node (ref "Z") (pin "1@2") (pinfunction "1_1@2") (pintype "passive"))
    )
    (net (code "25") (name "GRN_DELAY") (class "Default")
      (node (ref "E2") (pin "13") (pinfunction "Q_13") (pintype "output"))
      (node (ref "E3") (pin "1") (pinfunction "IN/GCLR_1") (pintype "input"))
      (node (ref "TP2") (pin "TP") (pinfunction "TP_TP") (pintype "input"))
    )
    (net (code "26") (name "INITIALIZE") (class "Default")
      (node (ref "E3") (pin "25") (pinfunction "IO17_25") (pintype "bidirectional"))
      (node (ref "OMNIBUS") (pin "CR1") (pinfunction "1_CR1") (pintype "bidirectional"))
    )
    (net (code "27") (name "INTENS") (class "Default")
      (node (ref "D3") (pin "A") (pinfunction "A_A") (pintype "passive"))
      (node (ref "R78") (pin "1") (pinfunction "1_1") (pintype "passive"))
      (node (ref "R79") (pin "1") (pinfunction "1_1") (pintype "passive"))
      (node (ref "S1") (pin "2") (pinfunction "P_2") (pintype "passive"))
    )
    (net (code "28") (name "N$27") (class "Default")
      (node (ref "D1") (pin "A") (pinfunction "A_A") (pintype "passive"))
      (node (ref "E3") (pin "61") (pinfunction "IO45_61") (pintype "bidirectional"))
      (node (ref "R1") (pin "1") (pinfunction "1_1") (pintype "passive"))
    )
    (net (code "29") (name "N$35") (class "Default")
      (node (ref "E1") (pin "13") (pinfunction "Q_13") (pintype "output"))
      (node (ref "E3") (pin "54") (pinfunction "IO39_54") (pintype "bidirectional"))
    )
    (net (code "30") (name "Net-(D2-PadC)") (class "Default")
      (node (ref "D2") (pin "C") (pinfunction "C_C") (pintype "passive"))
      (node (ref "R9") (pin "1") (pinfunction "1_1") (pintype "passive"))
      (node (ref "W3") (pin "1") (pinfunction "1_1") (pintype "passive"))
    )
    (net (code "31") (name "Net-(DELAY-O)") (class "Default")
      (node (ref "C39") (pin "1") (pinfunction "1_1") (pintype "passive"))
      (node (ref "DELAY") (pin "1") (pinfunction "O_1") (pintype "passive"))
    )
    (net (code "32") (name "Net-(DELAY-P)") (class "Default")
      (node (ref "DELAY") (pin "2") (pinfunction "P_2") (pintype "passive"))
      (node (ref "E4") (pin "13") (pinfunction "R/C_13") (pintype "input"))
      (node (ref "W3") (pin "2") (pinfunction "2_2") (pintype "passive"))
      (node (ref "W4") (pin "1") (pinfunction "1_1") (pintype "passive"))
    )
    (net (code "33") (name "Net-(DELAY-S)") (class "Default")
      (node (ref "C38") (pin "1") (pinfunction "1_1") (pintype "passive"))
      (node (ref "DELAY") (pin "3") (pinfunction "S_3") (pintype "passive"))
    )
    (net (code "34") (name "Net-(E1A-C)") (class "Default")
      (node (ref "C36") (pin "1") (pinfunction "1_1") (pintype "passive"))
      (node (ref "E1") (pin "14") (pinfunction "C_14") (pintype "input"))
    )
    (net (code "35") (name "Net-(E1A-R{slash}C)") (class "Default")
      (node (ref "C36") (pin "2") (pinfunction "2_2") (pintype "passive"))
      (node (ref "E1") (pin "15") (pinfunction "R/C_15") (pintype "input"))
      (node (ref "R4") (pin "1") (pinfunction "1_1") (pintype "passive"))
    )
    (net (code "36") (name "Net-(E1B-A)") (class "Default")
      (node (ref "E1") (pin "9") (pinfunction "A_9") (pintype "input"))
      (node (ref "Q1") (pin "3") (pinfunction "C_3") (pintype "passive"))
      (node (ref "R15") (pin "1") (pinfunction "1_1") (pintype "passive"))
    )
    (net (code "37") (name "Net-(E1B-B)") (class "Default")
      (node (ref "E1") (pin "10") (pinfunction "B_10") (pintype "input"))
      (node (ref "E1") (pin "11") (pinfunction "CLR_11") (pintype "input"))
      (node (ref "R22") (pin "1") (pinfunction "1_1") (pintype "passive"))
    )
    (net (code "38") (name "Net-(E1B-C)") (class "Default")
      (node (ref "C37") (pin "1") (pinfunction "1_1") (pintype "passive"))
      (node (ref "E1") (pin "6") (pinfunction "C_6") (pintype "input"))
    )
    (net (code "39") (name "Net-(E1B-R{slash}C)") (class "Default")
      (node (ref "C37") (pin "2") (pinfunction "2_2") (pintype "passive"))
      (node (ref "E1") (pin "7") (pinfunction "R/C_7") (pintype "input"))
      (node (ref "R7") (pin "1") (pinfunction "1_1") (pintype "passive"))
    )
    (net (code "40") (name "Net-(E2A-C)") (class "Default")
      (node (ref "C34") (pin "1") (pinfunction "1_1") (pintype "passive"))
      (node (ref "C35") (pin "1") (pinfunction "1_1") (pintype "passive"))
      (node (ref "C35A") (pin "1") (pinfunction "1_1") (pintype "passive"))
      (node (ref "E2") (pin "14") (pinfunction "C_14") (pintype "input"))
    )
    (net (code "41") (name "Net-(E2A-R{slash}C)") (class "Default")
      (node (ref "C34") (pin "2") (pinfunction "2_2") (pintype "passive"))
      (node (ref "C35") (pin "2") (pinfunction "2_2") (pintype "passive"))
      (node (ref "C35A") (pin "2") (pinfunction "2_2") (pintype "passive"))
      (node (ref "E2") (pin "15") (pinfunction "R/C_15") (pintype "input"))
      (node (ref "R19") (pin "1") (pinfunction "1_1") (pintype "passive"))
    )
    (net (code "42") (name "Net-(E2B-C)") (class "Default")
      (node (ref "C33") (pin "1") (pinfunction "1_1") (pintype "passive"))
      (node (ref "E2") (pin "6") (pinfunction "C_6") (pintype "input"))
    )
    (net (code "43") (name "Net-(E2B-R{slash}C)") (class "Default")
      (node (ref "C33") (pin "2") (pinfunction "2_2") (pintype "passive"))
      (node (ref "E2") (pin "7") (pinfunction "R/C_7") (pintype "input"))
      (node (ref "R20") (pin "1") (pinfunction "1_1") (pintype "passive"))
    )
    (net (code "44") (name "Net-(E4A-C)") (class "Default")
      (node (ref "C38") (pin "2") (pinfunction "2_2") (pintype "passive"))
      (node (ref "C39") (pin "2") (pinfunction "2_2") (pintype "passive"))
      (node (ref "E4") (pin "11") (pinfunction "C_11") (pintype "input"))
    )
    (net (code "45") (name "Net-(E5-OUT1)") (class "Default")
      (node (ref "C41") (pin "2") (pinfunction "2_2") (pintype "passive"))
      (node (ref "E5") (pin "1") (pinfunction "OUT1_1") (pintype "output"))
      (node (ref "E6") (pin "2") (pinfunction "-IN_2") (pintype "input"))
    )
    (net (code "46") (name "Net-(E5-RFB)") (class "Default")
      (node (ref "C41") (pin "1") (pinfunction "1_1") (pintype "passive"))
      (node (ref "E5") (pin "20") (pinfunction "RFB_20") (pintype "input"))
      (node (ref "E6") (pin "1") (pinfunction "OUT_1") (pintype "output"))
      (node (ref "R2") (pin "1") (pinfunction "1_1") (pintype "passive"))
    )
    (net (code "47") (name "Net-(E6B--IN)") (class "Default")
      (node (ref "E6") (pin "6") (pinfunction "-IN_6") (pintype "input"))
      (node (ref "R2") (pin "2") (pinfunction "2_2") (pintype "passive"))
      (node (ref "R3") (pin "1") (pinfunction "1_1") (pintype "passive"))
      (node (ref "R5") (pin "1") (pinfunction "1_1") (pintype "passive"))
    )
    (net (code "48") (name "Net-(E7-OUT1)") (class "Default")
      (node (ref "C42") (pin "2") (pinfunction "2_2") (pintype "passive"))
      (node (ref "E7") (pin "1") (pinfunction "OUT1_1") (pintype "output"))
      (node (ref "E8") (pin "2") (pinfunction "-IN_2") (pintype "input"))
    )
    (net (code "49") (name "Net-(E7-RFB)") (class "Default")
      (node (ref "C42") (pin "1") (pinfunction "1_1") (pintype "passive"))
      (node (ref "E7") (pin "20") (pinfunction "RFB_20") (pintype "input"))
      (node (ref "E8") (pin "1") (pinfunction "OUT_1") (pintype "output"))
      (node (ref "R6") (pin "1") (pinfunction "1_1") (pintype "passive"))
    )
    (net (code "50") (name "Net-(E8B--IN)") (class "Default")
      (node (ref "E8") (pin "6") (pinfunction "-IN_6") (pintype "input"))
      (node (ref "R11") (pin "1") (pinfunction "1_1") (pintype "passive"))
      (node (ref "R12") (pin "1") (pinfunction "1_1") (pintype "passive"))
      (node (ref "R6") (pin "2") (pinfunction "2_2") (pintype "passive"))
    )
    (net (code "51") (name "Net-(E15A-C)") (class "Default")
      (node (ref "C40") (pin "2") (pinfunction "2_2") (pintype "passive"))
      (node (ref "E15") (pin "11") (pinfunction "C_11") (pintype "input"))
    )
    (net (code "52") (name "Net-(E15A-R{slash}C)") (class "Default")
      (node (ref "C40") (pin "1") (pinfunction "1_1") (pintype "passive"))
      (node (ref "D1") (pin "C") (pinfunction "C_C") (pintype "passive"))
      (node (ref "E15") (pin "13") (pinfunction "R/C_13") (pintype "input"))
      (node (ref "R18") (pin "1") (pinfunction "1_1") (pintype "passive"))
    )
    (net (code "53") (name "Net-(Q1-B)") (class "Default")
      (node (ref "Q1") (pin "2") (pinfunction "B_2") (pintype "passive"))
      (node (ref "R14") (pin "2") (pinfunction "2_2") (pintype "passive"))
    )
    (net (code "54") (name "Net-(Q13-B)") (class "Default")
      (node (ref "Q13") (pin "2") (pinfunction "B_2") (pintype "passive"))
      (node (ref "R83") (pin "2") (pinfunction "2_2") (pintype "passive"))
    )
    (net (code "55") (name "Net-(Q13-C)") (class "Default")
      (node (ref "C64") (pin "1") (pinfunction "1_1") (pintype "passive"))
      (node (ref "Q13") (pin "3") (pinfunction "C_3") (pintype "passive"))
      (node (ref "R82") (pin "1") (pinfunction "1_1") (pintype "passive"))
    )
    (net (code "56") (name "Net-(Q13-E)") (class "Default")
      (node (ref "Q13") (pin "1") (pinfunction "E_1") (pintype "passive"))
      (node (ref "Q14") (pin "1") (pinfunction "E_1") (pintype "passive"))
      (node (ref "R86") (pin "2") (pinfunction "2_2") (pintype "passive"))
      (node (ref "R87") (pin "1") (pinfunction "1_1") (pintype "passive"))
    )
    (net (code "57") (name "Net-(Q14-B)") (class "Default")
      (node (ref "C63") (pin "2") (pinfunction "2_2") (pintype "passive"))
      (node (ref "Q14") (pin "2") (pinfunction "B_2") (pintype "passive"))
      (node (ref "Q31") (pin "3") (pinfunction "C_3") (pintype "passive"))
      (node (ref "R83") (pin "1") (pinfunction "1_1") (pintype "passive"))
      (node (ref "R84") (pin "2") (pinfunction "2_2") (pintype "passive"))
      (node (ref "W5") (pin "2") (pinfunction "2_2") (pintype "passive"))
      (node (ref "W8") (pin "2") (pinfunction "2_2") (pintype "passive"))
    )
    (net (code "58") (name "Net-(Q14-C)") (class "Default")
      (node (ref "C65") (pin "1") (pinfunction "1_1") (pintype "passive"))
      (node (ref "Q14") (pin "3") (pinfunction "C_3") (pintype "passive"))
      (node (ref "R85") (pin "2") (pinfunction "2_2") (pintype "passive"))
    )
    (net (code "59") (name "Net-(Q31-B)") (class "Default")
      (node (ref "C63") (pin "1") (pinfunction "1_1") (pintype "passive"))
      (node (ref "D3") (pin "C") (pinfunction "C_C") (pintype "passive"))
      (node (ref "Q31") (pin "2") (pinfunction "B_2") (pintype "passive"))
      (node (ref "R79") (pin "2") (pinfunction "2_2") (pintype "passive"))
    )
    (net (code "60") (name "Net-(R10-Pad1)") (class "Default")
      (node (ref "R10") (pin "1") (pinfunction "1_1") (pintype "passive"))
      (node (ref "W4") (pin "2") (pinfunction "2_2") (pintype "passive"))
    )
    (net (code "61") (name "Net-(R80-Pad2)") (class "Default")
      (node (ref "R80") (pin "2") (pinfunction "2_2") (pintype "passive"))
      (node (ref "W5") (pin "1") (pinfunction "1_1") (pintype "passive"))
    )
    (net (code "62") (name "Net-(R81-Pad2)") (class "Default")
      (node (ref "R81") (pin "2") (pinfunction "2_2") (pintype "passive"))
      (node (ref "W8") (pin "1") (pinfunction "1_1") (pintype "passive"))
    )
    (net (code "63") (name "RED_DELAY") (class "Default")
      (node (ref "E2") (pin "5") (pinfunction "Q_5") (pintype "output"))
      (node (ref "E3") (pin "51") (pinfunction "IO37_51") (pintype "bidirectional"))
      (node (ref "TP1") (pin "TP") (pinfunction "TP_TP") (pintype "input"))
    )
    (net (code "64") (name "SET_DONE") (class "Default")
      (node (ref "E1") (pin "5") (pinfunction "Q_5") (pintype "output"))
      (node (ref "E3") (pin "52") (pinfunction "IO38_52") (pintype "bidirectional"))
    )
    (net (code "65") (name "TCK") (class "Default")
      (node (ref "E3") (pin "62") (pinfunction "TCK_62") (pintype "bidirectional"))
      (node (ref "ISP") (pin "1") (pinfunction "1_1") (pintype "passive"))
    )
    (net (code "66") (name "TDI") (class "Default")
      (node (ref "E3") (pin "14") (pinfunction "TDI_14") (pintype "bidirectional"))
      (node (ref "ISP") (pin "9") (pinfunction "9_9") (pintype "passive"))
    )
    (net (code "67") (name "TDO") (class "Default")
      (node (ref "E3") (pin "71") (pinfunction "TDO_71") (pintype "bidirectional"))
      (node (ref "ISP") (pin "3") (pinfunction "3_3") (pintype "passive"))
    )
    (net (code "68") (name "TMS") (class "Default")
      (node (ref "E3") (pin "23") (pinfunction "TMS_23") (pintype "bidirectional"))
      (node (ref "ISP") (pin "5") (pinfunction "5_5") (pintype "passive"))
    )
    (net (code "69") (name "TP3") (class "Default")
      (node (ref "E3") (pin "29") (pinfunction "IO20_29") (pintype "bidirectional"))
      (node (ref "OMNIBUS") (pin "CH2") (pinfunction "1_CH2") (pintype "bidirectional"))
    )
    (net (code "70") (name "VCC") (class "Default")
      (node (ref "C1") (pin "1") (pinfunction "1_1") (pintype "passive"))
      (node (ref "C13") (pin "+") (pinfunction "+_+") (pintype "passive"))
      (node (ref "C14") (pin "+") (pinfunction "+_+") (pintype "passive"))
      (node (ref "C15") (pin "+") (pinfunction "+_+") (pintype "passive"))
      (node (ref "C2") (pin "1") (pinfunction "1_1") (pintype "passive"))
      (node (ref "C3") (pin "1") (pinfunction "1_1") (pintype "passive"))
      (node (ref "C4") (pin "1") (pinfunction "1_1") (pintype "passive"))
      (node (ref "C5") (pin "1") (pinfunction "1_1") (pintype "passive"))
      (node (ref "C6") (pin "1") (pinfunction "1_1") (pintype "passive"))
      (node (ref "C7") (pin "1") (pinfunction "1_1") (pintype "passive"))
      (node (ref "C8") (pin "1") (pinfunction "1_1") (pintype "passive"))
      (node (ref "E1") (pin "2") (pinfunction "B_2") (pintype "input"))
      (node (ref "E1") (pin "3") (pinfunction "CLR_3") (pintype "input"))
      (node (ref "E15") (pin "3") (pinfunction "B1_3") (pintype "input"))
      (node (ref "E15") (pin "4") (pinfunction "B2_4") (pintype "input"))
      (node (ref "E15") (pin "5") (pinfunction "CLR_5") (pintype "input"))
      (node (ref "E2") (pin "11") (pinfunction "CLR_11") (pintype "input"))
      (node (ref "E2") (pin "2") (pinfunction "B_2") (pintype "input"))
      (node (ref "E2") (pin "3") (pinfunction "CLR_3") (pintype "input"))
      (node (ref "E4") (pin "3") (pinfunction "B1_3") (pintype "input"))
      (node (ref "E4") (pin "4") (pinfunction "B2_4") (pintype "input"))
      (node (ref "E4") (pin "5") (pinfunction "CLR_5") (pintype "input"))
      (node (ref "E5") (pin "18") (pinfunction "VDD_18") (pintype "power_in"))
      (node (ref "E7") (pin "18") (pinfunction "VDD_18") (pintype "power_in"))
      (node (ref "ISP") (pin "4") (pinfunction "4_4") (pintype "passive"))
      (node (ref "J1") (pin "SS") (pinfunction "37_SS") (pintype "bidirectional"))
      (node (ref "J1") (pin "UU") (pinfunction "39_UU") (pintype "bidirectional"))
      (node (ref "J2") (pin "SS") (pinfunction "37_SS") (pintype "bidirectional"))
      (node (ref "J2") (pin "UU") (pinfunction "39_UU") (pintype "bidirectional"))
      (node (ref "J3") (pin "1") (pinfunction "1_1") (pintype "bidirectional"))
      (node (ref "J4") (pin "1") (pinfunction "1_1") (pintype "bidirectional"))
      (node (ref "OMNIBUS") (pin "AA2") (pinfunction "1_AA2") (pintype "bidirectional"))
      (node (ref "OMNIBUS") (pin "BA2") (pinfunction "1_BA2") (pintype "bidirectional"))
      (node (ref "OMNIBUS") (pin "CA2") (pinfunction "1_CA2") (pintype "bidirectional"))
      (node (ref "OSC") (pin "8") (pinfunction "VCC_8") (pintype "power_in"))
      (node (ref "OSC1") (pin "14") (pinfunction "VCC_14") (pintype "power_in"))
      (node (ref "Q31") (pin "1") (pinfunction "E_1") (pintype "passive"))
      (node (ref "R1") (pin "2") (pinfunction "2_2") (pintype "passive"))
      (node (ref "R10") (pin "2") (pinfunction "2_2") (pintype "passive"))
      (node (ref "R15") (pin "2") (pinfunction "2_2") (pintype "passive"))
      (node (ref "R18") (pin "2") (pinfunction "2_2") (pintype "passive"))
      (node (ref "R19") (pin "2") (pinfunction "2_2") (pintype "passive"))
      (node (ref "R20") (pin "2") (pinfunction "2_2") (pintype "passive"))
      (node (ref "R22") (pin "2") (pinfunction "2_2") (pintype "passive"))
      (node (ref "R4") (pin "2") (pinfunction "2_2") (pintype "passive"))
      (node (ref "R7") (pin "2") (pinfunction "2_2") (pintype "passive"))
      (node (ref "R78") (pin "2") (pinfunction "2_2") (pintype "passive"))
      (node (ref "R8") (pin "2") (pinfunction "2_2") (pintype "passive"))
      (node (ref "R80") (pin "1") (pinfunction "1_1") (pintype "passive"))
      (node (ref "R81") (pin "1") (pinfunction "1_1") (pintype "passive"))
      (node (ref "R82") (pin "2") (pinfunction "2_2") (pintype "passive"))
      (node (ref "R9") (pin "2") (pinfunction "2_2") (pintype "passive"))
      (node (ref "RN1") (pin "1") (pinfunction "1_1") (pintype "passive"))
    )
    (net (code "71") (name "VCCINT") (class "Default")
      (node (ref "C10") (pin "1") (pinfunction "1_1") (pintype "passive"))
      (node (ref "C9") (pin "1") (pinfunction "1_1") (pintype "passive"))
      (node (ref "J4") (pin "2") (pinfunction "2_2") (pintype "bidirectional"))
    )
    (net (code "72") (name "VCCIO") (class "Default")
      (node (ref "C11") (pin "1") (pinfunction "1_1") (pintype "passive"))
      (node (ref "C12") (pin "1") (pinfunction "1_1") (pintype "passive"))
      (node (ref "J3") (pin "2") (pinfunction "2_2") (pintype "bidirectional"))
    )
    (net (code "73") (name "X_ANALOG") (class "Default")
      (node (ref "E6") (pin "7") (pinfunction "OUT_7") (pintype "output"))
      (node (ref "J1") (pin "D") (pinfunction "4_D") (pintype "bidirectional"))
      (node (ref "R5") (pin "2") (pinfunction "2_2") (pintype "passive"))
      (node (ref "X") (pin "2") (pinfunction "2_2") (pintype "passive"))
    )
    (net (code "74") (name "Y_ANALOG") (class "Default")
      (node (ref "E8") (pin "7") (pinfunction "OUT_7") (pintype "output"))
      (node (ref "J1") (pin "L") (pinfunction "10_L") (pintype "bidirectional"))
      (node (ref "R12") (pin "2") (pinfunction "2_2") (pintype "passive"))
      (node (ref "Y") (pin "2") (pinfunction "2_2") (pintype "passive"))
    )
    (net (code "75") (name "Z_AXIS") (class "Default")
      (node (ref "J1") (pin "X") (pinfunction "20_X") (pintype "bidirectional"))
      (node (ref "R87") (pin "2") (pinfunction "2_2") (pintype "passive"))
      (node (ref "Z") (pin "2") (pinfunction "2_2") (pintype "passive"))
    )
    (net (code "76") (name "unconnected-(E1A-~{Q}-Pad4)") (class "Default")
      (node (ref "E1") (pin "4") (pinfunction "~{Q}_4") (pintype "output"))
    )
    (net (code "77") (name "unconnected-(E1B-~{Q}-Pad12)") (class "Default")
      (node (ref "E1") (pin "12") (pinfunction "~{Q}_12") (pintype "output"))
    )
    (net (code "78") (name "unconnected-(E2A-~{Q}-Pad4)") (class "Default")
      (node (ref "E2") (pin "4") (pinfunction "~{Q}_4") (pintype "output"))
    )
    (net (code "79") (name "unconnected-(E2B-~{Q}-Pad12)") (class "Default")
      (node (ref "E2") (pin "12") (pinfunction "~{Q}_12") (pintype "output"))
    )
    (net (code "80") (name "unconnected-(E4A-Q-Pad8)") (class "Default")
      (node (ref "E4") (pin "8") (pinfunction "Q_8") (pintype "output"))
    )
    (net (code "81") (name "unconnected-(E4A-R-Pad9)") (class "Default")
      (node (ref "E4") (pin "9") (pinfunction "R_9") (pintype "input"))
    )
    (net (code "82") (name "unconnected-(E15A-R-Pad9)") (class "Default")
      (node (ref "E15") (pin "9") (pinfunction "R_9") (pintype "input"))
    )
    (net (code "83") (name "unconnected-(ISP-Pad6)") (class "Default")
      (node (ref "ISP") (pin "6") (pinfunction "6_6") (pintype "passive"))
    )
    (net (code "84") (name "unconnected-(ISP-Pad7)") (class "Default")
      (node (ref "ISP") (pin "7") (pinfunction "7_7") (pintype "passive"))
    )
    (net (code "85") (name "unconnected-(ISP-Pad8)") (class "Default")
      (node (ref "ISP") (pin "8") (pinfunction "8_8") (pintype "passive"))
    )
    (net (code "86") (name "unconnected-(J1-2-PadB)") (class "Default")
      (node (ref "J1") (pin "B") (pinfunction "2_B") (pintype "bidirectional"))
    )
    (net (code "87") (name "unconnected-(J1-14-PadR)") (class "Default")
      (node (ref "J1") (pin "R") (pinfunction "14_R") (pintype "bidirectional"))
    )
    (net (code "88") (name "unconnected-(J1-16-PadT)") (class "Default")
      (node (ref "J1") (pin "T") (pinfunction "16_T") (pintype "bidirectional"))
    )
    (net (code "89") (name "unconnected-(J1-36-PadRR)") (class "Default")
      (node (ref "J1") (pin "RR") (pinfunction "36_RR") (pintype "bidirectional"))
    )
    (net (code "90") (name "unconnected-(J1-38-PadTT)") (class "Default")
      (node (ref "J1") (pin "TT") (pinfunction "38_TT") (pintype "bidirectional"))
    )
    (net (code "91") (name "unconnected-(J1-40-PadVV)") (class "Default")
      (node (ref "J1") (pin "VV") (pinfunction "40_VV") (pintype "bidirectional"))
    )
    (net (code "92") (name "unconnected-(J2-10-PadL)") (class "Default")
      (node (ref "J2") (pin "L") (pinfunction "10_L") (pintype "bidirectional"))
    )
    (net (code "93") (name "unconnected-(J2-12-PadN)") (class "Default")
      (node (ref "J2") (pin "N") (pinfunction "12_N") (pintype "bidirectional"))
    )
    (net (code "94") (name "unconnected-(J2-14-PadR)") (class "Default")
      (node (ref "J2") (pin "R") (pinfunction "14_R") (pintype "bidirectional"))
    )
    (net (code "95") (name "unconnected-(J2-16-PadT)") (class "Default")
      (node (ref "J2") (pin "T") (pinfunction "16_T") (pintype "bidirectional"))
    )
    (net (code "96") (name "unconnected-(J2-26-PadDD)") (class "Default")
      (node (ref "J2") (pin "DD") (pinfunction "26_DD") (pintype "bidirectional"))
    )
    (net (code "97") (name "unconnected-(J2-28-PadFF)") (class "Default")
      (node (ref "J2") (pin "FF") (pinfunction "28_FF") (pintype "bidirectional"))
    )
    (net (code "98") (name "unconnected-(J2-30-PadJJ)") (class "Default")
      (node (ref "J2") (pin "JJ") (pinfunction "30_JJ") (pintype "bidirectional"))
    )
    (net (code "99") (name "unconnected-(J2-32-PadLL)") (class "Default")
      (node (ref "J2") (pin "LL") (pinfunction "32_LL") (pintype "bidirectional"))
    )
    (net (code "100") (name "unconnected-(J2-34-PadNN)") (class "Default")
      (node (ref "J2") (pin "NN") (pinfunction "34_NN") (pintype "bidirectional"))
    )
    (net (code "101") (name "unconnected-(J2-36-PadRR)") (class "Default")
      (node (ref "J2") (pin "RR") (pinfunction "36_RR") (pintype "bidirectional"))
    )
    (net (code "102") (name "unconnected-(J2-38-PadTT)") (class "Default")
      (node (ref "J2") (pin "TT") (pinfunction "38_TT") (pintype "bidirectional"))
    )
    (net (code "103") (name "unconnected-(J2-40-PadVV)") (class "Default")
      (node (ref "J2") (pin "VV") (pinfunction "40_VV") (pintype "bidirectional"))
    )
    (net (code "104") (name "~{B_DIXY}") (class "Default")
      (node (ref "E15") (pin "1") (pinfunction "A1_1") (pintype "input"))
      (node (ref "E15") (pin "2") (pinfunction "A2_2") (pintype "input"))
      (node (ref "E3") (pin "55") (pinfunction "IO40_55") (pintype "bidirectional"))
    )
    (net (code "105") (name "~{C0}") (class "Default")
      (node (ref "E3") (pin "31") (pinfunction "IO22_31") (pintype "bidirectional"))
      (node (ref "OMNIBUS") (pin "CE1") (pinfunction "1_CE1") (pintype "bidirectional"))
    )
    (net (code "106") (name "~{C1}") (class "Default")
      (node (ref "E3") (pin "30") (pinfunction "IO21_30") (pintype "bidirectional"))
      (node (ref "OMNIBUS") (pin "CH1") (pinfunction "1_CH1") (pintype "bidirectional"))
    )
    (net (code "107") (name "~{CHAN}") (class "Default")
      (node (ref "E3") (pin "57") (pinfunction "IO42_57") (pintype "bidirectional"))
      (node (ref "J1") (pin "Z") (pinfunction "22_Z") (pintype "bidirectional"))
    )
    (net (code "108") (name "~{COL_RED}") (class "Default")
      (node (ref "E3") (pin "56") (pinfunction "IO41_56") (pintype "bidirectional"))
      (node (ref "J1") (pin "DD") (pinfunction "26_DD") (pintype "bidirectional"))
    )
    (net (code "109") (name "~{DATA0}") (class "Default")
      (node (ref "E3") (pin "49") (pinfunction "IO35_49") (pintype "bidirectional"))
      (node (ref "OMNIBUS") (pin "AR1") (pinfunction "1_AR1") (pintype "bidirectional"))
    )
    (net (code "110") (name "~{DATA1}") (class "Default")
      (node (ref "E3") (pin "48") (pinfunction "IO34_48") (pintype "bidirectional"))
      (node (ref "OMNIBUS") (pin "AS1") (pinfunction "1_AS1") (pintype "bidirectional"))
    )
    (net (code "111") (name "~{DATA2}") (class "Default")
      (node (ref "E3") (pin "46") (pinfunction "IO33_46") (pintype "bidirectional"))
      (node (ref "OMNIBUS") (pin "AU1") (pinfunction "1_AU1") (pintype "bidirectional"))
    )
    (net (code "112") (name "~{DATA3}") (class "Default")
      (node (ref "E3") (pin "45") (pinfunction "IO/PD2_45") (pintype "bidirectional"))
      (node (ref "OMNIBUS") (pin "AV1") (pinfunction "1_AV1") (pintype "bidirectional"))
    )
    (net (code "113") (name "~{DATA4}") (class "Default")
      (node (ref "E3") (pin "37") (pinfunction "IO27_37") (pintype "bidirectional"))
      (node (ref "OMNIBUS") (pin "BR1") (pinfunction "1_BR1") (pintype "bidirectional"))
    )
    (net (code "114") (name "~{DATA5}") (class "Default")
      (node (ref "E3") (pin "36") (pinfunction "IO26_36") (pintype "bidirectional"))
      (node (ref "OMNIBUS") (pin "BS1") (pinfunction "1_BS1") (pintype "bidirectional"))
    )
    (net (code "115") (name "~{DATA6}") (class "Default")
      (node (ref "E3") (pin "35") (pinfunction "IO25_35") (pintype "bidirectional"))
      (node (ref "OMNIBUS") (pin "BU1") (pinfunction "1_BU1") (pintype "bidirectional"))
    )
    (net (code "116") (name "~{DATA7}") (class "Default")
      (node (ref "E3") (pin "34") (pinfunction "IO24_34") (pintype "bidirectional"))
      (node (ref "OMNIBUS") (pin "BV1") (pinfunction "1_BV1") (pintype "bidirectional"))
    )
    (net (code "117") (name "~{DATA8}") (class "Default")
      (node (ref "E3") (pin "17") (pinfunction "IO11_17") (pintype "bidirectional"))
      (node (ref "OMNIBUS") (pin "DR1") (pinfunction "1_DR1") (pintype "bidirectional"))
    )
    (net (code "118") (name "~{DATA9}") (class "Default")
      (node (ref "E3") (pin "16") (pinfunction "IO10_16") (pintype "bidirectional"))
      (node (ref "OMNIBUS") (pin "DS1") (pinfunction "1_DS1") (pintype "bidirectional"))
    )
    (net (code "119") (name "~{DATA10}") (class "Default")
      (node (ref "E3") (pin "15") (pinfunction "IO9_15") (pintype "bidirectional"))
      (node (ref "OMNIBUS") (pin "DU1") (pinfunction "1_DU1") (pintype "bidirectional"))
    )
    (net (code "120") (name "~{DATA11}") (class "Default")
      (node (ref "E3") (pin "12") (pinfunction "IO/PD1_12") (pintype "bidirectional"))
      (node (ref "OMNIBUS") (pin "DV1") (pinfunction "1_DV1") (pintype "bidirectional"))
    )
    (net (code "121") (name "~{DEL_1}") (class "Default")
      (node (ref "E15") (pin "6") (pinfunction "~{Q}_6") (pintype "output"))
      (node (ref "E3") (pin "84") (pinfunction "IN/OE1_84") (pintype "input"))
      (node (ref "S1") (pin "1") (pinfunction "O_1") (pintype "passive"))
    )
    (net (code "122") (name "~{DI02}") (class "Default")
      (node (ref "E3") (pin "64") (pinfunction "IO47_64") (pintype "bidirectional"))
      (node (ref "E5") (pin "4") (pinfunction "DB11_4") (pintype "input"))
      (node (ref "E7") (pin "4") (pinfunction "DB11_4") (pintype "input"))
    )
    (net (code "123") (name "~{DLY_DONE}") (class "Default")
      (node (ref "E1") (pin "1") (pinfunction "A_1") (pintype "input"))
      (node (ref "E3") (pin "63") (pinfunction "IO46_63") (pintype "bidirectional"))
    )
    (net (code "124") (name "~{ERASE_INTERVAL}") (class "Default")
      (node (ref "J1") (pin "NN") (pinfunction "34_NN") (pintype "bidirectional"))
      (node (ref "R14") (pin "1") (pinfunction "1_1") (pintype "passive"))
    )
    (net (code "125") (name "~{ERASE}") (class "Default")
      (node (ref "E3") (pin "58") (pinfunction "IO43_58") (pintype "bidirectional"))
      (node (ref "J1") (pin "FF") (pinfunction "28_FF") (pintype "bidirectional"))
    )
    (net (code "126") (name "~{INTERNAL_IO}") (class "Default")
      (node (ref "E3") (pin "28") (pinfunction "IO19_28") (pintype "bidirectional"))
      (node (ref "OMNIBUS") (pin "CL1") (pinfunction "1_CL1") (pintype "bidirectional"))
    )
    (net (code "127") (name "~{INTERRUPT}") (class "Default")
      (node (ref "E3") (pin "27") (pinfunction "IO18_27") (pintype "bidirectional"))
      (node (ref "OMNIBUS") (pin "CP1") (pinfunction "1_CP1") (pintype "bidirectional"))
    )
    (net (code "128") (name "~{LD_DEL}") (class "Default")
      (node (ref "E3") (pin "81") (pinfunction "IO/GCLK3_81") (pintype "bidirectional"))
      (node (ref "E4") (pin "6") (pinfunction "~{Q}_6") (pintype "output"))
    )
    (net (code "129") (name "~{LOAD_X}") (class "Default")
      (node (ref "E3") (pin "77") (pinfunction "IO57_77") (pintype "bidirectional"))
      (node (ref "E4") (pin "1") (pinfunction "A1_1") (pintype "input"))
      (node (ref "E5") (pin "16") (pinfunction "CS_16") (pintype "input"))
      (node (ref "E5") (pin "17") (pinfunction "WR_17") (pintype "input"))
    )
    (net (code "130") (name "~{LOAD_Y}") (class "Default")
      (node (ref "E3") (pin "79") (pinfunction "IO58_79") (pintype "bidirectional"))
      (node (ref "E4") (pin "2") (pinfunction "A2_2") (pintype "input"))
      (node (ref "E7") (pin "16") (pinfunction "CS_16") (pintype "input"))
      (node (ref "E7") (pin "17") (pinfunction "WR_17") (pintype "input"))
    )
    (net (code "131") (name "~{MD3}") (class "Default")
      (node (ref "E3") (pin "50") (pinfunction "IO36_50") (pintype "bidirectional"))
      (node (ref "OMNIBUS") (pin "AP1") (pinfunction "1_AP1") (pintype "bidirectional"))
    )
    (net (code "132") (name "~{MD4}") (class "Default")
      (node (ref "E3") (pin "44") (pinfunction "IO31_44") (pintype "bidirectional"))
      (node (ref "OMNIBUS") (pin "BK1") (pinfunction "1_BK1") (pintype "bidirectional"))
    )
    (net (code "133") (name "~{MD5}") (class "Default")
      (node (ref "E3") (pin "41") (pinfunction "IO30_41") (pintype "bidirectional"))
      (node (ref "OMNIBUS") (pin "BL1") (pinfunction "1_BL1") (pintype "bidirectional"))
    )
    (net (code "134") (name "~{MD6}") (class "Default")
      (node (ref "E3") (pin "40") (pinfunction "IO29_40") (pintype "bidirectional"))
      (node (ref "OMNIBUS") (pin "BM1") (pinfunction "1_BM1") (pintype "bidirectional"))
    )
    (net (code "135") (name "~{MD7}") (class "Default")
      (node (ref "E3") (pin "39") (pinfunction "IO28_39") (pintype "bidirectional"))
      (node (ref "OMNIBUS") (pin "BP1") (pinfunction "1_BP1") (pintype "bidirectional"))
    )
    (net (code "136") (name "~{MD8}") (class "Default")
      (node (ref "E3") (pin "22") (pinfunction "IO15_22") (pintype "bidirectional"))
      (node (ref "OMNIBUS") (pin "DK1") (pinfunction "1_DK1") (pintype "bidirectional"))
    )
    (net (code "137") (name "~{MD9}") (class "Default")
      (node (ref "E3") (pin "21") (pinfunction "IO14_21") (pintype "bidirectional"))
      (node (ref "OMNIBUS") (pin "DL1") (pinfunction "1_DL1") (pintype "bidirectional"))
    )
    (net (code "138") (name "~{MD10}") (class "Default")
      (node (ref "E3") (pin "20") (pinfunction "IO13_20") (pintype "bidirectional"))
      (node (ref "OMNIBUS") (pin "DM1") (pinfunction "1_DM1") (pintype "bidirectional"))
    )
    (net (code "139") (name "~{MD11}") (class "Default")
      (node (ref "E3") (pin "18") (pinfunction "IO12_18") (pintype "bidirectional"))
      (node (ref "OMNIBUS") (pin "DP1") (pinfunction "1_DP1") (pintype "bidirectional"))
    )
    (net (code "140") (name "~{NON_STORE}") (class "Default")
      (node (ref "E3") (pin "80") (pinfunction "IO59_80") (pintype "bidirectional"))
      (node (ref "J1") (pin "LL") (pinfunction "32_LL") (pintype "bidirectional"))
    )
    (net (code "141") (name "~{PAUSE}") (class "Default")
      (node (ref "E3") (pin "33") (pinfunction "IO23_33") (pintype "bidirectional"))
      (node (ref "OMNIBUS") (pin "CD1") (pinfunction "1_CD1") (pintype "bidirectional"))
    )
    (net (code "142") (name "~{SKIP}") (class "Default")
      (node (ref "E3") (pin "24") (pinfunction "IO16_24") (pintype "bidirectional"))
      (node (ref "OMNIBUS") (pin "CS1") (pinfunction "1_CS1") (pintype "bidirectional"))
    )
    (net (code "143") (name "~{WRITE_THRU}") (class "Default")
      (node (ref "E3") (pin "60") (pinfunction "IO44_60") (pintype "bidirectional"))
      (node (ref "J1") (pin "JJ") (pinfunction "30_JJ") (pintype "bidirectional"))
    )
  )
)
